# 11_DDR2.net
KiCad netlist of a schematic drawn in Altium Designer
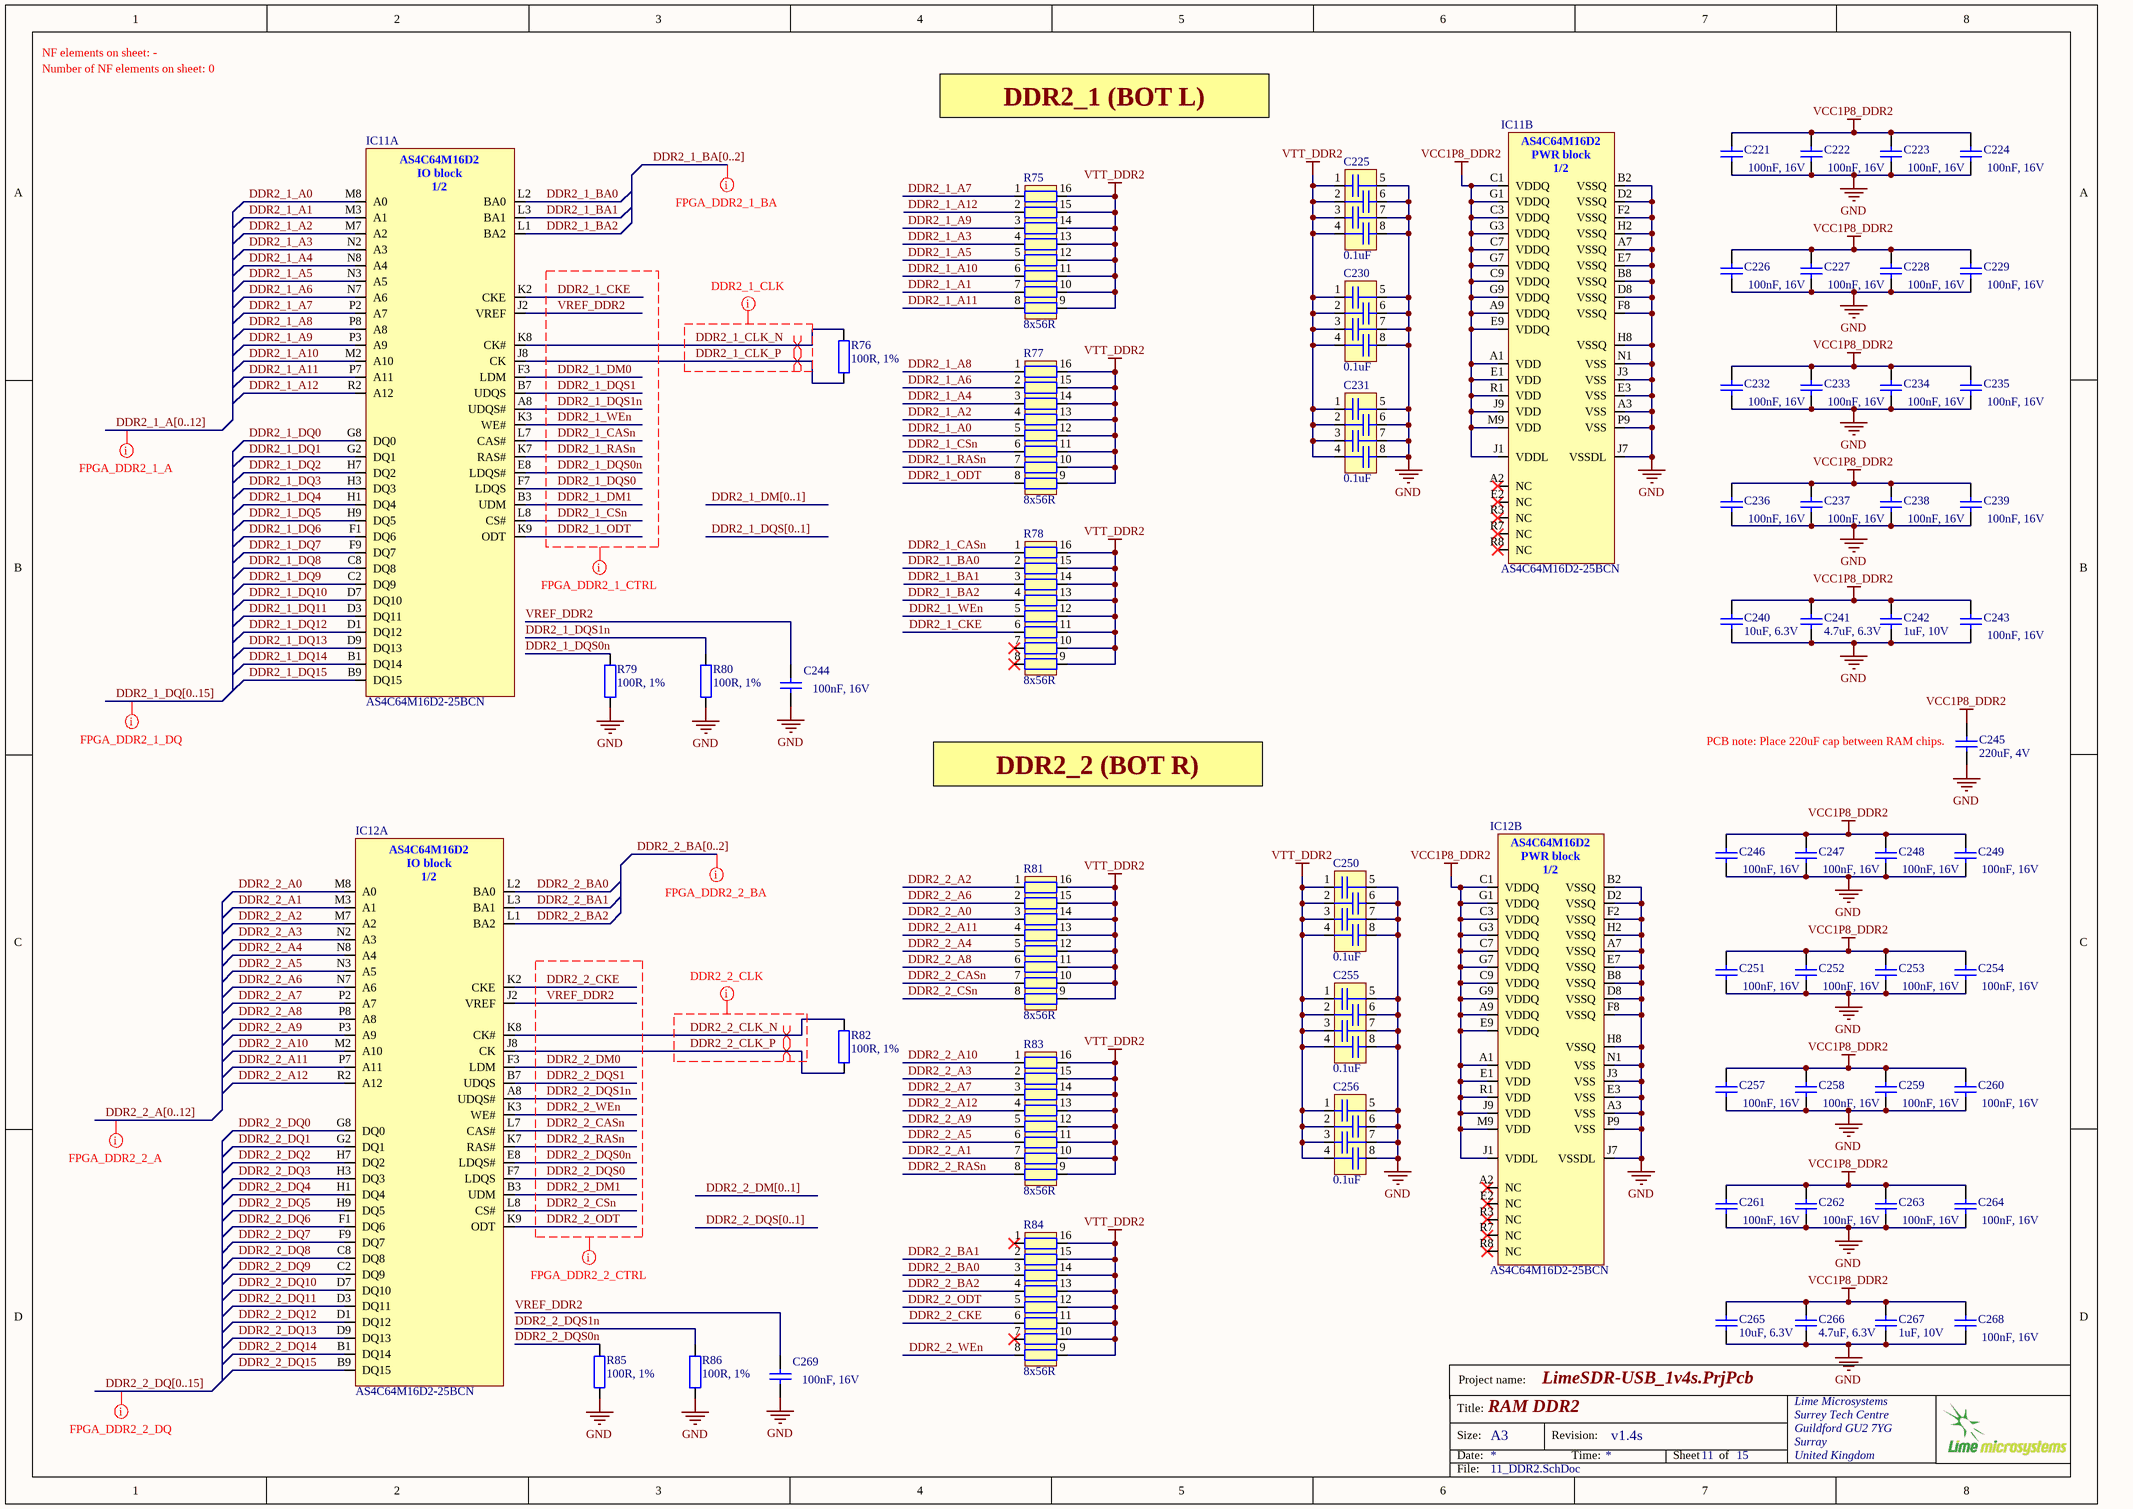
[diagram p0: 11_DDR2.SchDoc]

(export (version "E")
  (design (tool "Eeschema 10.0.6"))
  (components
    (comp (ref "C221")
      (value "100nF, 16V")
      (footprint "CAP0402")
      (fields
        (field (name "TOLERANCE") "10 %")
        (field (name "MANUFACTURER") "Murata Electronics")
        (field (name "MANUFACTURER PART NUMBER") "GRM155R71C104KA88D")
      )
      (libsource (lib "LimeFPGAboard_schLib") (part "Cap_0603"))
    )
    (comp (ref "C222")
      (value "100nF, 16V")
      (footprint "CAP0402")
      (fields
        (field (name "TOLERANCE") "10 %")
        (field (name "MANUFACTURER") "Murata Electronics")
        (field (name "MANUFACTURER PART NUMBER") "GRM155R71C104KA88D")
      )
      (libsource (lib "LimeFPGAboard_schLib") (part "Cap_0603"))
    )
    (comp (ref "C223")
      (value "100nF, 16V")
      (footprint "CAP0402")
      (fields
        (field (name "TOLERANCE") "10 %")
        (field (name "MANUFACTURER") "Murata Electronics")
        (field (name "MANUFACTURER PART NUMBER") "GRM155R71C104KA88D")
      )
      (libsource (lib "LimeFPGAboard_schLib") (part "Cap_0603"))
    )
    (comp (ref "C224")
      (value "100nF, 16V")
      (footprint "CAP0402")
      (fields
        (field (name "TOLERANCE") "10 %")
        (field (name "MANUFACTURER") "Murata Electronics")
        (field (name "MANUFACTURER PART NUMBER") "GRM155R71C104KA88D")
      )
      (libsource (lib "LimeFPGAboard_schLib") (part "Cap_0603"))
    )
    (comp (ref "C225")
      (value "0.1uF")
      (footprint "CKCA43X7R1C104M100AA")
      (fields (field (name "MANUFACTURER") "TDK") (field (name "TOLERANCE") "20 %"))
      (libsource (lib "LimeFPGAboard_schLib") (part "4X_cap_array_1206"))
    )
    (comp (ref "C226")
      (value "100nF, 16V")
      (footprint "CAP0402")
      (fields
        (field (name "TOLERANCE") "10 %")
        (field (name "MANUFACTURER") "Murata Electronics")
        (field (name "MANUFACTURER PART NUMBER") "GRM155R71C104KA88D")
      )
      (libsource (lib "LimeFPGAboard_schLib") (part "Cap_0603"))
    )
    (comp (ref "C227")
      (value "100nF, 16V")
      (footprint "CAP0402")
      (fields
        (field (name "TOLERANCE") "10 %")
        (field (name "MANUFACTURER") "Murata Electronics")
        (field (name "MANUFACTURER PART NUMBER") "GRM155R71C104KA88D")
      )
      (libsource (lib "LimeFPGAboard_schLib") (part "Cap_0603"))
    )
    (comp (ref "C228")
      (value "100nF, 16V")
      (footprint "CAP0402")
      (fields
        (field (name "TOLERANCE") "10 %")
        (field (name "MANUFACTURER") "Murata Electronics")
        (field (name "MANUFACTURER PART NUMBER") "GRM155R71C104KA88D")
      )
      (libsource (lib "LimeFPGAboard_schLib") (part "Cap_0603"))
    )
    (comp (ref "C229")
      (value "100nF, 16V")
      (footprint "CAP0402")
      (fields
        (field (name "TOLERANCE") "10 %")
        (field (name "MANUFACTURER") "Murata Electronics")
        (field (name "MANUFACTURER PART NUMBER") "GRM155R71C104KA88D")
      )
      (libsource (lib "LimeFPGAboard_schLib") (part "Cap_0603"))
    )
    (comp (ref "C230")
      (value "0.1uF")
      (footprint "CKCA43X7R1C104M100AA")
      (fields (field (name "MANUFACTURER") "TDK") (field (name "TOLERANCE") "20 %"))
      (libsource (lib "LimeFPGAboard_schLib") (part "4X_cap_array_1206"))
    )
    (comp (ref "C231")
      (value "0.1uF")
      (footprint "CKCA43X7R1C104M100AA")
      (fields (field (name "MANUFACTURER") "TDK") (field (name "TOLERANCE") "20 %"))
      (libsource (lib "LimeFPGAboard_schLib") (part "4X_cap_array_1206"))
    )
    (comp (ref "C232")
      (value "100nF, 16V")
      (footprint "CAP0402")
      (fields
        (field (name "TOLERANCE") "10 %")
        (field (name "MANUFACTURER") "Murata Electronics")
        (field (name "MANUFACTURER PART NUMBER") "GRM155R71C104KA88D")
      )
      (libsource (lib "LimeFPGAboard_schLib") (part "Cap_0603"))
    )
    (comp (ref "C233")
      (value "100nF, 16V")
      (footprint "CAP0402")
      (fields
        (field (name "TOLERANCE") "10 %")
        (field (name "MANUFACTURER") "Murata Electronics")
        (field (name "MANUFACTURER PART NUMBER") "GRM155R71C104KA88D")
      )
      (libsource (lib "LimeFPGAboard_schLib") (part "Cap_0603"))
    )
    (comp (ref "C234")
      (value "100nF, 16V")
      (footprint "CAP0402")
      (fields
        (field (name "TOLERANCE") "10 %")
        (field (name "MANUFACTURER") "Murata Electronics")
        (field (name "MANUFACTURER PART NUMBER") "GRM155R71C104KA88D")
      )
      (libsource (lib "LimeFPGAboard_schLib") (part "Cap_0603"))
    )
    (comp (ref "C235")
      (value "100nF, 16V")
      (footprint "CAP0402")
      (fields
        (field (name "TOLERANCE") "10 %")
        (field (name "MANUFACTURER") "Murata Electronics")
        (field (name "MANUFACTURER PART NUMBER") "GRM155R71C104KA88D")
      )
      (libsource (lib "LimeFPGAboard_schLib") (part "Cap_0603"))
    )
    (comp (ref "C236")
      (value "100nF, 16V")
      (footprint "CAP0402")
      (fields
        (field (name "TOLERANCE") "10 %")
        (field (name "MANUFACTURER") "Murata Electronics")
        (field (name "MANUFACTURER PART NUMBER") "GRM155R71C104KA88D")
      )
      (libsource (lib "LimeFPGAboard_schLib") (part "Cap_0603"))
    )
    (comp (ref "C237")
      (value "100nF, 16V")
      (footprint "CAP0402")
      (fields
        (field (name "TOLERANCE") "10 %")
        (field (name "MANUFACTURER") "Murata Electronics")
        (field (name "MANUFACTURER PART NUMBER") "GRM155R71C104KA88D")
      )
      (libsource (lib "LimeFPGAboard_schLib") (part "Cap_0603"))
    )
    (comp (ref "C238")
      (value "100nF, 16V")
      (footprint "CAP0402")
      (fields
        (field (name "TOLERANCE") "10 %")
        (field (name "MANUFACTURER") "Murata Electronics")
        (field (name "MANUFACTURER PART NUMBER") "GRM155R71C104KA88D")
      )
      (libsource (lib "LimeFPGAboard_schLib") (part "Cap_0603"))
    )
    (comp (ref "C239")
      (value "100nF, 16V")
      (footprint "CAP0402")
      (fields
        (field (name "TOLERANCE") "10 %")
        (field (name "MANUFACTURER") "Murata Electronics")
        (field (name "MANUFACTURER PART NUMBER") "GRM155R71C104KA88D")
      )
      (libsource (lib "LimeFPGAboard_schLib") (part "Cap_0603"))
    )
    (comp (ref "C240")
      (value "10uF, 6.3V")
      (footprint "CAP0603")
      (fields (field (name "TOLERANCE") "±20%") (field (name "MANUFACTURER") "Yageo"))
      (libsource (lib "LimeFPGAboard_schLib") (part "Cap_0603"))
    )
    (comp (ref "C241")
      (value "4.7uF, 6.3V")
      (footprint "CAP0402")
      (fields
        (field (name "MANUFACTURER") "Murata Electronics North America")
        (field (name "TOLERANCE") "±20%")
        (field (name "MANUFACTURER PART NUMBER") "GRM155R60J475ME87D")
      )
      (libsource (lib "LimeMicroAltiumLib_schLib") (part "Cap_0402"))
    )
    (comp (ref "C242")
      (value "1uF, 10V")
      (footprint "CAP0402")
      (fields (field (name "MANUFACTURER") "TDK"))
      (libsource (lib "LimeMicroAltiumLib_schLib") (part "Cap_0402"))
    )
    (comp (ref "C243")
      (value "100nF, 16V")
      (footprint "CAP0402")
      (fields
        (field (name "TOLERANCE") "10 %")
        (field (name "MANUFACTURER") "Murata Electronics")
        (field (name "MANUFACTURER PART NUMBER") "GRM155R71C104KA88D")
      )
      (libsource (lib "LimeFPGAboard_schLib") (part "Cap_0603"))
    )
    (comp (ref "C244")
      (value "100nF, 16V")
      (footprint "CAP0402")
      (fields
        (field (name "TOLERANCE") "10 %")
        (field (name "MANUFACTURER") "Murata Electronics")
        (field (name "MANUFACTURER PART NUMBER") "GRM155R71C104KA88D")
      )
      (libsource (lib "LimeFPGAboard_schLib") (part "Cap_0603"))
    )
    (comp (ref "C245")
      (value "220uF, 4V")
      (footprint "CAP1206")
      (fields
        (field (name "MANUFACTURER PART NUMBER") "GRM31CR60G227ME11L")
        (field (name "MANUFACTURER") "Murata Electronics North America")
        (field (name "TOLERANCE") "±20%")
      )
      (libsource (lib "LimeFPGAboard_schLib") (part "Cap_1206"))
    )
    (comp (ref "C246")
      (value "100nF, 16V")
      (footprint "CAP0402")
      (fields
        (field (name "TOLERANCE") "10 %")
        (field (name "MANUFACTURER") "Murata Electronics")
        (field (name "MANUFACTURER PART NUMBER") "GRM155R71C104KA88D")
      )
      (libsource (lib "LimeFPGAboard_schLib") (part "Cap_0603"))
    )
    (comp (ref "C247")
      (value "100nF, 16V")
      (footprint "CAP0402")
      (fields
        (field (name "TOLERANCE") "10 %")
        (field (name "MANUFACTURER") "Murata Electronics")
        (field (name "MANUFACTURER PART NUMBER") "GRM155R71C104KA88D")
      )
      (libsource (lib "LimeFPGAboard_schLib") (part "Cap_0603"))
    )
    (comp (ref "C248")
      (value "100nF, 16V")
      (footprint "CAP0402")
      (fields
        (field (name "TOLERANCE") "10 %")
        (field (name "MANUFACTURER") "Murata Electronics")
        (field (name "MANUFACTURER PART NUMBER") "GRM155R71C104KA88D")
      )
      (libsource (lib "LimeFPGAboard_schLib") (part "Cap_0603"))
    )
    (comp (ref "C249")
      (value "100nF, 16V")
      (footprint "CAP0402")
      (fields
        (field (name "TOLERANCE") "10 %")
        (field (name "MANUFACTURER") "Murata Electronics")
        (field (name "MANUFACTURER PART NUMBER") "GRM155R71C104KA88D")
      )
      (libsource (lib "LimeFPGAboard_schLib") (part "Cap_0603"))
    )
    (comp (ref "C250")
      (value "0.1uF")
      (footprint "CKCA43X7R1C104M100AA")
      (fields (field (name "MANUFACTURER") "TDK") (field (name "TOLERANCE") "20 %"))
      (libsource (lib "LimeFPGAboard_schLib") (part "4X_cap_array_1206"))
    )
    (comp (ref "C251")
      (value "100nF, 16V")
      (footprint "CAP0402")
      (fields
        (field (name "TOLERANCE") "10 %")
        (field (name "MANUFACTURER") "Murata Electronics")
        (field (name "MANUFACTURER PART NUMBER") "GRM155R71C104KA88D")
      )
      (libsource (lib "LimeFPGAboard_schLib") (part "Cap_0603"))
    )
    (comp (ref "C252")
      (value "100nF, 16V")
      (footprint "CAP0402")
      (fields
        (field (name "TOLERANCE") "10 %")
        (field (name "MANUFACTURER") "Murata Electronics")
        (field (name "MANUFACTURER PART NUMBER") "GRM155R71C104KA88D")
      )
      (libsource (lib "LimeFPGAboard_schLib") (part "Cap_0603"))
    )
    (comp (ref "C253")
      (value "100nF, 16V")
      (footprint "CAP0402")
      (fields
        (field (name "TOLERANCE") "10 %")
        (field (name "MANUFACTURER") "Murata Electronics")
        (field (name "MANUFACTURER PART NUMBER") "GRM155R71C104KA88D")
      )
      (libsource (lib "LimeFPGAboard_schLib") (part "Cap_0603"))
    )
    (comp (ref "C254")
      (value "100nF, 16V")
      (footprint "CAP0402")
      (fields
        (field (name "TOLERANCE") "10 %")
        (field (name "MANUFACTURER") "Murata Electronics")
        (field (name "MANUFACTURER PART NUMBER") "GRM155R71C104KA88D")
      )
      (libsource (lib "LimeFPGAboard_schLib") (part "Cap_0603"))
    )
    (comp (ref "C255")
      (value "0.1uF")
      (footprint "CKCA43X7R1C104M100AA")
      (fields (field (name "MANUFACTURER") "TDK") (field (name "TOLERANCE") "20 %"))
      (libsource (lib "LimeFPGAboard_schLib") (part "4X_cap_array_1206"))
    )
    (comp (ref "C256")
      (value "0.1uF")
      (footprint "CKCA43X7R1C104M100AA")
      (fields (field (name "MANUFACTURER") "TDK") (field (name "TOLERANCE") "20 %"))
      (libsource (lib "LimeFPGAboard_schLib") (part "4X_cap_array_1206"))
    )
    (comp (ref "C257")
      (value "100nF, 16V")
      (footprint "CAP0402")
      (fields
        (field (name "TOLERANCE") "10 %")
        (field (name "MANUFACTURER") "Murata Electronics")
        (field (name "MANUFACTURER PART NUMBER") "GRM155R71C104KA88D")
      )
      (libsource (lib "LimeFPGAboard_schLib") (part "Cap_0603"))
    )
    (comp (ref "C258")
      (value "100nF, 16V")
      (footprint "CAP0402")
      (fields
        (field (name "TOLERANCE") "10 %")
        (field (name "MANUFACTURER") "Murata Electronics")
        (field (name "MANUFACTURER PART NUMBER") "GRM155R71C104KA88D")
      )
      (libsource (lib "LimeFPGAboard_schLib") (part "Cap_0603"))
    )
    (comp (ref "C259")
      (value "100nF, 16V")
      (footprint "CAP0402")
      (fields
        (field (name "TOLERANCE") "10 %")
        (field (name "MANUFACTURER") "Murata Electronics")
        (field (name "MANUFACTURER PART NUMBER") "GRM155R71C104KA88D")
      )
      (libsource (lib "LimeFPGAboard_schLib") (part "Cap_0603"))
    )
    (comp (ref "C260")
      (value "100nF, 16V")
      (footprint "CAP0402")
      (fields
        (field (name "TOLERANCE") "10 %")
        (field (name "MANUFACTURER") "Murata Electronics")
        (field (name "MANUFACTURER PART NUMBER") "GRM155R71C104KA88D")
      )
      (libsource (lib "LimeFPGAboard_schLib") (part "Cap_0603"))
    )
    (comp (ref "C261")
      (value "100nF, 16V")
      (footprint "CAP0402")
      (fields
        (field (name "TOLERANCE") "10 %")
        (field (name "MANUFACTURER") "Murata Electronics")
        (field (name "MANUFACTURER PART NUMBER") "GRM155R71C104KA88D")
      )
      (libsource (lib "LimeFPGAboard_schLib") (part "Cap_0603"))
    )
    (comp (ref "C262")
      (value "100nF, 16V")
      (footprint "CAP0402")
      (fields
        (field (name "TOLERANCE") "10 %")
        (field (name "MANUFACTURER") "Murata Electronics")
        (field (name "MANUFACTURER PART NUMBER") "GRM155R71C104KA88D")
      )
      (libsource (lib "LimeFPGAboard_schLib") (part "Cap_0603"))
    )
    (comp (ref "C263")
      (value "100nF, 16V")
      (footprint "CAP0402")
      (fields
        (field (name "TOLERANCE") "10 %")
        (field (name "MANUFACTURER") "Murata Electronics")
        (field (name "MANUFACTURER PART NUMBER") "GRM155R71C104KA88D")
      )
      (libsource (lib "LimeFPGAboard_schLib") (part "Cap_0603"))
    )
    (comp (ref "C264")
      (value "100nF, 16V")
      (footprint "CAP0402")
      (fields
        (field (name "TOLERANCE") "10 %")
        (field (name "MANUFACTURER") "Murata Electronics")
        (field (name "MANUFACTURER PART NUMBER") "GRM155R71C104KA88D")
      )
      (libsource (lib "LimeFPGAboard_schLib") (part "Cap_0603"))
    )
    (comp (ref "C265")
      (value "10uF, 6.3V")
      (footprint "CAP0603")
      (fields (field (name "TOLERANCE") "±20%") (field (name "MANUFACTURER") "Yageo"))
      (libsource (lib "LimeFPGAboard_schLib") (part "Cap_0603"))
    )
    (comp (ref "C266")
      (value "4.7uF, 6.3V")
      (footprint "CAP0402")
      (fields
        (field (name "MANUFACTURER") "Murata Electronics North America")
        (field (name "TOLERANCE") "±20%")
        (field (name "MANUFACTURER PART NUMBER") "GRM155R60J475ME87D")
      )
      (libsource (lib "LimeMicroAltiumLib_schLib") (part "Cap_0402"))
    )
    (comp (ref "C267")
      (value "1uF, 10V")
      (footprint "CAP0402")
      (fields (field (name "MANUFACTURER") "TDK"))
      (libsource (lib "LimeMicroAltiumLib_schLib") (part "Cap_0402"))
    )
    (comp (ref "C268")
      (value "100nF, 16V")
      (footprint "CAP0402")
      (fields
        (field (name "TOLERANCE") "10 %")
        (field (name "MANUFACTURER") "Murata Electronics")
        (field (name "MANUFACTURER PART NUMBER") "GRM155R71C104KA88D")
      )
      (libsource (lib "LimeFPGAboard_schLib") (part "Cap_0603"))
    )
    (comp (ref "C269")
      (value "100nF, 16V")
      (footprint "CAP0402")
      (fields
        (field (name "TOLERANCE") "10 %")
        (field (name "MANUFACTURER") "Murata Electronics")
        (field (name "MANUFACTURER PART NUMBER") "GRM155R71C104KA88D")
      )
      (libsource (lib "LimeFPGAboard_schLib") (part "Cap_0603"))
    )
    (comp (ref "IC11")
      (value "AS4C64M16D2-25BCN")
      (footprint "AS4C64M16D2")
      (fields (field (name "MANUFACTURER") "Alliance Memory, Inc."))
      (libsource (lib "LimeMicroAltiumLib_schLib") (part "AS4C64M16D2-25BCN"))
    )
    (comp (ref "IC12")
      (value "AS4C64M16D2-25BCN")
      (footprint "AS4C64M16D2")
      (fields (field (name "MANUFACTURER") "Alliance Memory, Inc."))
      (libsource (lib "LimeMicroAltiumLib_schLib") (part "AS4C64M16D2-25BCN"))
    )
    (comp (ref "R75")
      (value "8x56R")
      (footprint "EXB2HV")
      (fields (field (name "MANUFACTURER") "PANASONIC ELECTRONIC COMPONENTS"))
      (libsource (lib "LimeFPGAboard_schLib") (part "8X_resistor_array_0402"))
    )
    (comp (ref "R76")
      (value "100R, 1%")
      (footprint "RES0402")
      (fields (field (name "TOLERANCE") "±1%") (field (name "MANUFACTURER") "Stackpole Electronics Inc."))
      (libsource (lib "LimeFPGAboard_schLib") (part "Res_0402"))
    )
    (comp (ref "R77")
      (value "8x56R")
      (footprint "EXB2HV")
      (fields (field (name "MANUFACTURER") "PANASONIC ELECTRONIC COMPONENTS"))
      (libsource (lib "LimeFPGAboard_schLib") (part "8X_resistor_array_0402"))
    )
    (comp (ref "R78")
      (value "8x56R")
      (footprint "EXB2HV")
      (fields (field (name "MANUFACTURER") "PANASONIC ELECTRONIC COMPONENTS"))
      (libsource (lib "LimeFPGAboard_schLib") (part "8X_resistor_array_0402"))
    )
    (comp (ref "R79")
      (value "100R, 1%")
      (footprint "RES0402")
      (fields (field (name "TOLERANCE") "±1%") (field (name "MANUFACTURER") "Stackpole Electronics Inc."))
      (libsource (lib "LimeFPGAboard_schLib") (part "Res_0402"))
    )
    (comp (ref "R80")
      (value "100R, 1%")
      (footprint "RES0402")
      (fields (field (name "TOLERANCE") "±1%") (field (name "MANUFACTURER") "Stackpole Electronics Inc."))
      (libsource (lib "LimeFPGAboard_schLib") (part "Res_0402"))
    )
    (comp (ref "R81")
      (value "8x56R")
      (footprint "EXB2HV")
      (fields (field (name "MANUFACTURER") "PANASONIC ELECTRONIC COMPONENTS"))
      (libsource (lib "LimeFPGAboard_schLib") (part "8X_resistor_array_0402"))
    )
    (comp (ref "R82")
      (value "100R, 1%")
      (footprint "RES0402")
      (fields (field (name "TOLERANCE") "±1%") (field (name "MANUFACTURER") "Stackpole Electronics Inc."))
      (libsource (lib "LimeFPGAboard_schLib") (part "Res_0402"))
    )
    (comp (ref "R83")
      (value "8x56R")
      (footprint "EXB2HV")
      (fields (field (name "MANUFACTURER") "PANASONIC ELECTRONIC COMPONENTS"))
      (libsource (lib "LimeFPGAboard_schLib") (part "8X_resistor_array_0402"))
    )
    (comp (ref "R84")
      (value "8x56R")
      (footprint "EXB2HV")
      (fields (field (name "MANUFACTURER") "PANASONIC ELECTRONIC COMPONENTS"))
      (libsource (lib "LimeFPGAboard_schLib") (part "8X_resistor_array_0402"))
    )
    (comp (ref "R85")
      (value "100R, 1%")
      (footprint "RES0402")
      (fields (field (name "TOLERANCE") "±1%") (field (name "MANUFACTURER") "Stackpole Electronics Inc."))
      (libsource (lib "LimeFPGAboard_schLib") (part "Res_0402"))
    )
    (comp (ref "R86")
      (value "100R, 1%")
      (footprint "RES0402")
      (fields (field (name "TOLERANCE") "±1%") (field (name "MANUFACTURER") "Stackpole Electronics Inc."))
      (libsource (lib "LimeFPGAboard_schLib") (part "Res_0402"))
    )
  )
  (nets
    (net (code "1") (name "/DDR2_1_A0") (class "Default")
      (node (ref "IC11") (pin "M8") (pinfunction "A0_M8") (pintype "passive"))
      (node (ref "R77") (pin "5") (pinfunction "5_5") (pintype "passive"))
    )
    (net (code "2") (name "/DDR2_1_A1") (class "Default")
      (node (ref "IC11") (pin "M3") (pinfunction "A1_M3") (pintype "passive"))
      (node (ref "R75") (pin "7") (pinfunction "7_7") (pintype "passive"))
    )
    (net (code "3") (name "/DDR2_1_A2") (class "Default")
      (node (ref "IC11") (pin "M7") (pinfunction "A2_M7") (pintype "passive"))
      (node (ref "R77") (pin "4") (pinfunction "4_4") (pintype "passive"))
    )
    (net (code "4") (name "/DDR2_1_A3") (class "Default")
      (node (ref "IC11") (pin "N2") (pinfunction "A3_N2") (pintype "passive"))
      (node (ref "R75") (pin "4") (pinfunction "4_4") (pintype "passive"))
    )
    (net (code "5") (name "/DDR2_1_A4") (class "Default")
      (node (ref "IC11") (pin "N8") (pinfunction "A4_N8") (pintype "passive"))
      (node (ref "R77") (pin "3") (pinfunction "3_3") (pintype "passive"))
    )
    (net (code "6") (name "/DDR2_1_A5") (class "Default")
      (node (ref "IC11") (pin "N3") (pinfunction "A5_N3") (pintype "passive"))
      (node (ref "R75") (pin "5") (pinfunction "5_5") (pintype "passive"))
    )
    (net (code "7") (name "/DDR2_1_A6") (class "Default")
      (node (ref "IC11") (pin "N7") (pinfunction "A6_N7") (pintype "passive"))
      (node (ref "R77") (pin "2") (pinfunction "2_2") (pintype "passive"))
    )
    (net (code "8") (name "/DDR2_1_A7") (class "Default")
      (node (ref "IC11") (pin "P2") (pinfunction "A7_P2") (pintype "passive"))
      (node (ref "R75") (pin "1") (pinfunction "1_1") (pintype "passive"))
    )
    (net (code "9") (name "/DDR2_1_A8") (class "Default")
      (node (ref "IC11") (pin "P8") (pinfunction "A8_P8") (pintype "passive"))
      (node (ref "R77") (pin "1") (pinfunction "1_1") (pintype "passive"))
    )
    (net (code "10") (name "/DDR2_1_A9") (class "Default")
      (node (ref "IC11") (pin "P3") (pinfunction "A9_P3") (pintype "passive"))
      (node (ref "R75") (pin "3") (pinfunction "3_3") (pintype "passive"))
    )
    (net (code "11") (name "/DDR2_1_A10") (class "Default")
      (node (ref "IC11") (pin "M2") (pinfunction "A10_M2") (pintype "passive"))
      (node (ref "R75") (pin "6") (pinfunction "6_6") (pintype "passive"))
    )
    (net (code "12") (name "/DDR2_1_A11") (class "Default")
      (node (ref "IC11") (pin "P7") (pinfunction "A11_P7") (pintype "passive"))
      (node (ref "R75") (pin "8") (pinfunction "8_8") (pintype "passive"))
    )
    (net (code "13") (name "/DDR2_1_A12") (class "Default")
      (node (ref "IC11") (pin "R2") (pinfunction "A12_R2") (pintype "passive"))
      (node (ref "R75") (pin "2") (pinfunction "2_2") (pintype "passive"))
    )
    (net (code "15") (name "/DDR2_1_BA0") (class "Default")
      (node (ref "IC11") (pin "L2") (pinfunction "BA0_L2") (pintype "passive"))
      (node (ref "R78") (pin "2") (pinfunction "2_2") (pintype "passive"))
    )
    (net (code "16") (name "/DDR2_1_BA1") (class "Default")
      (node (ref "IC11") (pin "L3") (pinfunction "BA1_L3") (pintype "passive"))
      (node (ref "R78") (pin "3") (pinfunction "3_3") (pintype "passive"))
    )
    (net (code "17") (name "/DDR2_1_BA2") (class "Default")
      (node (ref "IC11") (pin "L1") (pinfunction "BA2_L1") (pintype "passive"))
      (node (ref "R78") (pin "4") (pinfunction "4_4") (pintype "passive"))
    )
    (net (code "19") (name "/DDR2_1_CASn") (class "Default")
      (node (ref "IC11") (pin "L7") (pinfunction "CAS#_L7") (pintype "passive"))
      (node (ref "R78") (pin "1") (pinfunction "1_1") (pintype "passive"))
    )
    (net (code "20") (name "/DDR2_1_CKE") (class "Default")
      (node (ref "IC11") (pin "K2") (pinfunction "CKE_K2") (pintype "passive"))
      (node (ref "R78") (pin "6") (pinfunction "6_6") (pintype "passive"))
    )
    (net (code "21") (name "/DDR2_1_CLK_N") (class "Default")
      (node (ref "IC11") (pin "K8") (pinfunction "CK#_K8") (pintype "passive"))
      (node (ref "R76") (pin "2") (pinfunction "2_2") (pintype "passive"))
    )
    (net (code "22") (name "/DDR2_1_CLK_P") (class "Default")
      (node (ref "IC11") (pin "J8") (pinfunction "CK_J8") (pintype "passive"))
      (node (ref "R76") (pin "1") (pinfunction "1_1") (pintype "passive"))
    )
    (net (code "23") (name "/DDR2_1_CSn") (class "Default")
      (node (ref "IC11") (pin "L8") (pinfunction "CS#_L8") (pintype "passive"))
      (node (ref "R77") (pin "6") (pinfunction "6_6") (pintype "passive"))
    )
    (net (code "24") (name "/DDR2_1_DM0") (class "Default")
      (node (ref "IC11") (pin "F3") (pinfunction "LDM_F3") (pintype "passive"))
    )
    (net (code "25") (name "/DDR2_1_DM1") (class "Default")
      (node (ref "IC11") (pin "B3") (pinfunction "UDM_B3") (pintype "passive"))
    )
    (net (code "27") (name "/DDR2_1_DQ0") (class "Default")
      (node (ref "IC11") (pin "G8") (pinfunction "DQ0_G8") (pintype "passive"))
    )
    (net (code "28") (name "/DDR2_1_DQ1") (class "Default")
      (node (ref "IC11") (pin "G2") (pinfunction "DQ1_G2") (pintype "passive"))
    )
    (net (code "29") (name "/DDR2_1_DQ2") (class "Default")
      (node (ref "IC11") (pin "H7") (pinfunction "DQ2_H7") (pintype "passive"))
    )
    (net (code "30") (name "/DDR2_1_DQ3") (class "Default")
      (node (ref "IC11") (pin "H3") (pinfunction "DQ3_H3") (pintype "passive"))
    )
    (net (code "31") (name "/DDR2_1_DQ4") (class "Default")
      (node (ref "IC11") (pin "H1") (pinfunction "DQ4_H1") (pintype "passive"))
    )
    (net (code "32") (name "/DDR2_1_DQ5") (class "Default")
      (node (ref "IC11") (pin "H9") (pinfunction "DQ5_H9") (pintype "passive"))
    )
    (net (code "33") (name "/DDR2_1_DQ6") (class "Default")
      (node (ref "IC11") (pin "F1") (pinfunction "DQ6_F1") (pintype "passive"))
    )
    (net (code "34") (name "/DDR2_1_DQ7") (class "Default")
      (node (ref "IC11") (pin "F9") (pinfunction "DQ7_F9") (pintype "passive"))
    )
    (net (code "35") (name "/DDR2_1_DQ8") (class "Default")
      (node (ref "IC11") (pin "C8") (pinfunction "DQ8_C8") (pintype "passive"))
    )
    (net (code "36") (name "/DDR2_1_DQ9") (class "Default")
      (node (ref "IC11") (pin "C2") (pinfunction "DQ9_C2") (pintype "passive"))
    )
    (net (code "37") (name "/DDR2_1_DQ10") (class "Default")
      (node (ref "IC11") (pin "D7") (pinfunction "DQ10_D7") (pintype "passive"))
    )
    (net (code "38") (name "/DDR2_1_DQ11") (class "Default")
      (node (ref "IC11") (pin "D3") (pinfunction "DQ11_D3") (pintype "passive"))
    )
    (net (code "39") (name "/DDR2_1_DQ12") (class "Default")
      (node (ref "IC11") (pin "D1") (pinfunction "DQ12_D1") (pintype "passive"))
    )
    (net (code "40") (name "/DDR2_1_DQ13") (class "Default")
      (node (ref "IC11") (pin "D9") (pinfunction "DQ13_D9") (pintype "passive"))
    )
    (net (code "41") (name "/DDR2_1_DQ14") (class "Default")
      (node (ref "IC11") (pin "B1") (pinfunction "DQ14_B1") (pintype "passive"))
    )
    (net (code "42") (name "/DDR2_1_DQ15") (class "Default")
      (node (ref "IC11") (pin "B9") (pinfunction "DQ15_B9") (pintype "passive"))
    )
    (net (code "43") (name "/DDR2_1_DQS0") (class "Default")
      (node (ref "IC11") (pin "F7") (pinfunction "LDQS_F7") (pintype "passive"))
    )
    (net (code "44") (name "/DDR2_1_DQS0n") (class "Default")
      (node (ref "IC11") (pin "E8") (pinfunction "LDQS#_E8") (pintype "passive"))
      (node (ref "R79") (pin "2") (pinfunction "2_2") (pintype "passive"))
    )
    (net (code "45") (name "/DDR2_1_DQS1") (class "Default")
      (node (ref "IC11") (pin "B7") (pinfunction "UDQS_B7") (pintype "passive"))
    )
    (net (code "46") (name "/DDR2_1_DQS1n") (class "Default")
      (node (ref "IC11") (pin "A8") (pinfunction "UDQS#_A8") (pintype "passive"))
      (node (ref "R80") (pin "2") (pinfunction "2_2") (pintype "passive"))
    )
    (net (code "49") (name "/DDR2_1_ODT") (class "Default")
      (node (ref "IC11") (pin "K9") (pinfunction "ODT_K9") (pintype "passive"))
      (node (ref "R77") (pin "8") (pinfunction "8_8") (pintype "passive"))
    )
    (net (code "50") (name "/DDR2_1_RASn") (class "Default")
      (node (ref "IC11") (pin "K7") (pinfunction "RAS#_K7") (pintype "passive"))
      (node (ref "R77") (pin "7") (pinfunction "7_7") (pintype "passive"))
    )
    (net (code "51") (name "/DDR2_1_WEn") (class "Default")
      (node (ref "IC11") (pin "K3") (pinfunction "WE#_K3") (pintype "passive"))
      (node (ref "R78") (pin "5") (pinfunction "5_5") (pintype "passive"))
    )
    (net (code "52") (name "/DDR2_2_A0") (class "Default")
      (node (ref "IC12") (pin "M8") (pinfunction "A0_M8") (pintype "passive"))
      (node (ref "R81") (pin "3") (pinfunction "3_3") (pintype "passive"))
    )
    (net (code "53") (name "/DDR2_2_A1") (class "Default")
      (node (ref "IC12") (pin "M3") (pinfunction "A1_M3") (pintype "passive"))
      (node (ref "R83") (pin "7") (pinfunction "7_7") (pintype "passive"))
    )
    (net (code "54") (name "/DDR2_2_A2") (class "Default")
      (node (ref "IC12") (pin "M7") (pinfunction "A2_M7") (pintype "passive"))
      (node (ref "R81") (pin "1") (pinfunction "1_1") (pintype "passive"))
    )
    (net (code "55") (name "/DDR2_2_A3") (class "Default")
      (node (ref "IC12") (pin "N2") (pinfunction "A3_N2") (pintype "passive"))
      (node (ref "R83") (pin "2") (pinfunction "2_2") (pintype "passive"))
    )
    (net (code "56") (name "/DDR2_2_A4") (class "Default")
      (node (ref "IC12") (pin "N8") (pinfunction "A4_N8") (pintype "passive"))
      (node (ref "R81") (pin "5") (pinfunction "5_5") (pintype "passive"))
    )
    (net (code "57") (name "/DDR2_2_A5") (class "Default")
      (node (ref "IC12") (pin "N3") (pinfunction "A5_N3") (pintype "passive"))
      (node (ref "R83") (pin "6") (pinfunction "6_6") (pintype "passive"))
    )
    (net (code "58") (name "/DDR2_2_A6") (class "Default")
      (node (ref "IC12") (pin "N7") (pinfunction "A6_N7") (pintype "passive"))
      (node (ref "R81") (pin "2") (pinfunction "2_2") (pintype "passive"))
    )
    (net (code "59") (name "/DDR2_2_A7") (class "Default")
      (node (ref "IC12") (pin "P2") (pinfunction "A7_P2") (pintype "passive"))
      (node (ref "R83") (pin "3") (pinfunction "3_3") (pintype "passive"))
    )
    (net (code "60") (name "/DDR2_2_A8") (class "Default")
      (node (ref "IC12") (pin "P8") (pinfunction "A8_P8") (pintype "passive"))
      (node (ref "R81") (pin "6") (pinfunction "6_6") (pintype "passive"))
    )
    (net (code "61") (name "/DDR2_2_A9") (class "Default")
      (node (ref "IC12") (pin "P3") (pinfunction "A9_P3") (pintype "passive"))
      (node (ref "R83") (pin "5") (pinfunction "5_5") (pintype "passive"))
    )
    (net (code "62") (name "/DDR2_2_A10") (class "Default")
      (node (ref "IC12") (pin "M2") (pinfunction "A10_M2") (pintype "passive"))
      (node (ref "R83") (pin "1") (pinfunction "1_1") (pintype "passive"))
    )
    (net (code "63") (name "/DDR2_2_A11") (class "Default")
      (node (ref "IC12") (pin "P7") (pinfunction "A11_P7") (pintype "passive"))
      (node (ref "R81") (pin "4") (pinfunction "4_4") (pintype "passive"))
    )
    (net (code "64") (name "/DDR2_2_A12") (class "Default")
      (node (ref "IC12") (pin "R2") (pinfunction "A12_R2") (pintype "passive"))
      (node (ref "R83") (pin "4") (pinfunction "4_4") (pintype "passive"))
    )
    (net (code "66") (name "/DDR2_2_BA0") (class "Default")
      (node (ref "IC12") (pin "L2") (pinfunction "BA0_L2") (pintype "passive"))
      (node (ref "R84") (pin "3") (pinfunction "3_3") (pintype "passive"))
    )
    (net (code "67") (name "/DDR2_2_BA1") (class "Default")
      (node (ref "IC12") (pin "L3") (pinfunction "BA1_L3") (pintype "passive"))
      (node (ref "R84") (pin "2") (pinfunction "2_2") (pintype "passive"))
    )
    (net (code "68") (name "/DDR2_2_BA2") (class "Default")
      (node (ref "IC12") (pin "L1") (pinfunction "BA2_L1") (pintype "passive"))
      (node (ref "R84") (pin "4") (pinfunction "4_4") (pintype "passive"))
    )
    (net (code "70") (name "/DDR2_2_CASn") (class "Default")
      (node (ref "IC12") (pin "L7") (pinfunction "CAS#_L7") (pintype "passive"))
      (node (ref "R81") (pin "7") (pinfunction "7_7") (pintype "passive"))
    )
    (net (code "71") (name "/DDR2_2_CKE") (class "Default")
      (node (ref "IC12") (pin "K2") (pinfunction "CKE_K2") (pintype "passive"))
      (node (ref "R84") (pin "6") (pinfunction "6_6") (pintype "passive"))
    )
    (net (code "72") (name "/DDR2_2_CLK_N") (class "Default")
      (node (ref "IC12") (pin "K8") (pinfunction "CK#_K8") (pintype "passive"))
      (node (ref "R82") (pin "2") (pinfunction "2_2") (pintype "passive"))
    )
    (net (code "73") (name "/DDR2_2_CLK_P") (class "Default")
      (node (ref "IC12") (pin "J8") (pinfunction "CK_J8") (pintype "passive"))
      (node (ref "R82") (pin "1") (pinfunction "1_1") (pintype "passive"))
    )
    (net (code "74") (name "/DDR2_2_CSn") (class "Default")
      (node (ref "IC12") (pin "L8") (pinfunction "CS#_L8") (pintype "passive"))
      (node (ref "R81") (pin "8") (pinfunction "8_8") (pintype "passive"))
    )
    (net (code "75") (name "/DDR2_2_DM0") (class "Default")
      (node (ref "IC12") (pin "F3") (pinfunction "LDM_F3") (pintype "passive"))
    )
    (net (code "76") (name "/DDR2_2_DM1") (class "Default")
      (node (ref "IC12") (pin "B3") (pinfunction "UDM_B3") (pintype "passive"))
    )
    (net (code "78") (name "/DDR2_2_DQ0") (class "Default")
      (node (ref "IC12") (pin "G8") (pinfunction "DQ0_G8") (pintype "passive"))
    )
    (net (code "79") (name "/DDR2_2_DQ1") (class "Default")
      (node (ref "IC12") (pin "G2") (pinfunction "DQ1_G2") (pintype "passive"))
    )
    (net (code "80") (name "/DDR2_2_DQ2") (class "Default")
      (node (ref "IC12") (pin "H7") (pinfunction "DQ2_H7") (pintype "passive"))
    )
    (net (code "81") (name "/DDR2_2_DQ3") (class "Default")
      (node (ref "IC12") (pin "H3") (pinfunction "DQ3_H3") (pintype "passive"))
    )
    (net (code "82") (name "/DDR2_2_DQ4") (class "Default")
      (node (ref "IC12") (pin "H1") (pinfunction "DQ4_H1") (pintype "passive"))
    )
    (net (code "83") (name "/DDR2_2_DQ5") (class "Default")
      (node (ref "IC12") (pin "H9") (pinfunction "DQ5_H9") (pintype "passive"))
    )
    (net (code "84") (name "/DDR2_2_DQ6") (class "Default")
      (node (ref "IC12") (pin "F1") (pinfunction "DQ6_F1") (pintype "passive"))
    )
    (net (code "85") (name "/DDR2_2_DQ7") (class "Default")
      (node (ref "IC12") (pin "F9") (pinfunction "DQ7_F9") (pintype "passive"))
    )
    (net (code "86") (name "/DDR2_2_DQ8") (class "Default")
      (node (ref "IC12") (pin "C8") (pinfunction "DQ8_C8") (pintype "passive"))
    )
    (net (code "87") (name "/DDR2_2_DQ9") (class "Default")
      (node (ref "IC12") (pin "C2") (pinfunction "DQ9_C2") (pintype "passive"))
    )
    (net (code "88") (name "/DDR2_2_DQ10") (class "Default")
      (node (ref "IC12") (pin "D7") (pinfunction "DQ10_D7") (pintype "passive"))
    )
    (net (code "89") (name "/DDR2_2_DQ11") (class "Default")
      (node (ref "IC12") (pin "D3") (pinfunction "DQ11_D3") (pintype "passive"))
    )
    (net (code "90") (name "/DDR2_2_DQ12") (class "Default")
      (node (ref "IC12") (pin "D1") (pinfunction "DQ12_D1") (pintype "passive"))
    )
    (net (code "91") (name "/DDR2_2_DQ13") (class "Default")
      (node (ref "IC12") (pin "D9") (pinfunction "DQ13_D9") (pintype "passive"))
    )
    (net (code "92") (name "/DDR2_2_DQ14") (class "Default")
      (node (ref "IC12") (pin "B1") (pinfunction "DQ14_B1") (pintype "passive"))
    )
    (net (code "93") (name "/DDR2_2_DQ15") (class "Default")
      (node (ref "IC12") (pin "B9") (pinfunction "DQ15_B9") (pintype "passive"))
    )
    (net (code "94") (name "/DDR2_2_DQS0") (class "Default")
      (node (ref "IC12") (pin "F7") (pinfunction "LDQS_F7") (pintype "passive"))
    )
    (net (code "95") (name "/DDR2_2_DQS0n") (class "Default")
      (node (ref "IC12") (pin "E8") (pinfunction "LDQS#_E8") (pintype "passive"))
      (node (ref "R85") (pin "2") (pinfunction "2_2") (pintype "passive"))
    )
    (net (code "96") (name "/DDR2_2_DQS1") (class "Default")
      (node (ref "IC12") (pin "B7") (pinfunction "UDQS_B7") (pintype "passive"))
    )
    (net (code "97") (name "/DDR2_2_DQS1n") (class "Default")
      (node (ref "IC12") (pin "A8") (pinfunction "UDQS#_A8") (pintype "passive"))
      (node (ref "R86") (pin "2") (pinfunction "2_2") (pintype "passive"))
    )
    (net (code "100") (name "/DDR2_2_ODT") (class "Default")
      (node (ref "IC12") (pin "K9") (pinfunction "ODT_K9") (pintype "passive"))
      (node (ref "R84") (pin "5") (pinfunction "5_5") (pintype "passive"))
    )
    (net (code "101") (name "/DDR2_2_RASn") (class "Default")
      (node (ref "IC12") (pin "K7") (pinfunction "RAS#_K7") (pintype "passive"))
      (node (ref "R83") (pin "8") (pinfunction "8_8") (pintype "passive"))
    )
    (net (code "102") (name "/DDR2_2_WEn") (class "Default")
      (node (ref "IC12") (pin "K3") (pinfunction "WE#_K3") (pintype "passive"))
      (node (ref "R84") (pin "8") (pinfunction "8_8") (pintype "passive"))
    )
    (net (code "103") (name "/VREF_DDR2") (class "Default")
      (node (ref "C244") (pin "1") (pinfunction "1_1") (pintype "passive"))
      (node (ref "C269") (pin "1") (pinfunction "1_1") (pintype "passive"))
      (node (ref "IC11") (pin "J2") (pinfunction "VREF_J2") (pintype "passive"))
      (node (ref "IC12") (pin "J2") (pinfunction "VREF_J2") (pintype "passive"))
    )
    (net (code "104") (name "GND") (class "Default")
      (node (ref "C221") (pin "2") (pinfunction "2_2") (pintype "passive"))
      (node (ref "C222") (pin "2") (pinfunction "2_2") (pintype "passive"))
      (node (ref "C223") (pin "2") (pinfunction "2_2") (pintype "passive"))
      (node (ref "C224") (pin "2") (pinfunction "2_2") (pintype "passive"))
      (node (ref "C225") (pin "5") (pinfunction "5_5") (pintype "passive"))
      (node (ref "C225") (pin "6") (pinfunction "6_6") (pintype "passive"))
      (node (ref "C225") (pin "7") (pinfunction "7_7") (pintype "passive"))
      (node (ref "C225") (pin "8") (pinfunction "8_8") (pintype "passive"))
      (node (ref "C226") (pin "2") (pinfunction "2_2") (pintype "passive"))
      (node (ref "C227") (pin "2") (pinfunction "2_2") (pintype "passive"))
      (node (ref "C228") (pin "2") (pinfunction "2_2") (pintype "passive"))
      (node (ref "C229") (pin "2") (pinfunction "2_2") (pintype "passive"))
      (node (ref "C230") (pin "5") (pinfunction "5_5") (pintype "passive"))
      (node (ref "C230") (pin "6") (pinfunction "6_6") (pintype "passive"))
      (node (ref "C230") (pin "7") (pinfunction "7_7") (pintype "passive"))
      (node (ref "C230") (pin "8") (pinfunction "8_8") (pintype "passive"))
      (node (ref "C231") (pin "5") (pinfunction "5_5") (pintype "passive"))
      (node (ref "C231") (pin "6") (pinfunction "6_6") (pintype "passive"))
      (node (ref "C231") (pin "7") (pinfunction "7_7") (pintype "passive"))
      (node (ref "C231") (pin "8") (pinfunction "8_8") (pintype "passive"))
      (node (ref "C232") (pin "2") (pinfunction "2_2") (pintype "passive"))
      (node (ref "C233") (pin "2") (pinfunction "2_2") (pintype "passive"))
      (node (ref "C234") (pin "2") (pinfunction "2_2") (pintype "passive"))
      (node (ref "C235") (pin "2") (pinfunction "2_2") (pintype "passive"))
      (node (ref "C236") (pin "2") (pinfunction "2_2") (pintype "passive"))
      (node (ref "C237") (pin "2") (pinfunction "2_2") (pintype "passive"))
      (node (ref "C238") (pin "2") (pinfunction "2_2") (pintype "passive"))
      (node (ref "C239") (pin "2") (pinfunction "2_2") (pintype "passive"))
      (node (ref "C240") (pin "1") (pinfunction "1_1") (pintype "passive"))
      (node (ref "C241") (pin "1") (pinfunction "1_1") (pintype "passive"))
      (node (ref "C242") (pin "1") (pinfunction "1_1") (pintype "passive"))
      (node (ref "C243") (pin "2") (pinfunction "2_2") (pintype "passive"))
      (node (ref "C244") (pin "2") (pinfunction "2_2") (pintype "passive"))
      (node (ref "C245") (pin "1") (pinfunction "1_1") (pintype "passive"))
      (node (ref "C246") (pin "2") (pinfunction "2_2") (pintype "passive"))
      (node (ref "C247") (pin "2") (pinfunction "2_2") (pintype "passive"))
      (node (ref "C248") (pin "2") (pinfunction "2_2") (pintype "passive"))
      (node (ref "C249") (pin "2") (pinfunction "2_2") (pintype "passive"))
      (node (ref "C250") (pin "5") (pinfunction "5_5") (pintype "passive"))
      (node (ref "C250") (pin "6") (pinfunction "6_6") (pintype "passive"))
      (node (ref "C250") (pin "7") (pinfunction "7_7") (pintype "passive"))
      (node (ref "C250") (pin "8") (pinfunction "8_8") (pintype "passive"))
      (node (ref "C251") (pin "2") (pinfunction "2_2") (pintype "passive"))
      (node (ref "C252") (pin "2") (pinfunction "2_2") (pintype "passive"))
      (node (ref "C253") (pin "2") (pinfunction "2_2") (pintype "passive"))
      (node (ref "C254") (pin "2") (pinfunction "2_2") (pintype "passive"))
      (node (ref "C255") (pin "5") (pinfunction "5_5") (pintype "passive"))
      (node (ref "C255") (pin "6") (pinfunction "6_6") (pintype "passive"))
      (node (ref "C255") (pin "7") (pinfunction "7_7") (pintype "passive"))
      (node (ref "C255") (pin "8") (pinfunction "8_8") (pintype "passive"))
      (node (ref "C256") (pin "5") (pinfunction "5_5") (pintype "passive"))
      (node (ref "C256") (pin "6") (pinfunction "6_6") (pintype "passive"))
      (node (ref "C256") (pin "7") (pinfunction "7_7") (pintype "passive"))
      (node (ref "C256") (pin "8") (pinfunction "8_8") (pintype "passive"))
      (node (ref "C257") (pin "2") (pinfunction "2_2") (pintype "passive"))
      (node (ref "C258") (pin "2") (pinfunction "2_2") (pintype "passive"))
      (node (ref "C259") (pin "2") (pinfunction "2_2") (pintype "passive"))
      (node (ref "C260") (pin "2") (pinfunction "2_2") (pintype "passive"))
      (node (ref "C261") (pin "2") (pinfunction "2_2") (pintype "passive"))
      (node (ref "C262") (pin "2") (pinfunction "2_2") (pintype "passive"))
      (node (ref "C263") (pin "2") (pinfunction "2_2") (pintype "passive"))
      (node (ref "C264") (pin "2") (pinfunction "2_2") (pintype "passive"))
      (node (ref "C265") (pin "1") (pinfunction "1_1") (pintype "passive"))
      (node (ref "C266") (pin "1") (pinfunction "1_1") (pintype "passive"))
      (node (ref "C267") (pin "1") (pinfunction "1_1") (pintype "passive"))
      (node (ref "C268") (pin "2") (pinfunction "2_2") (pintype "passive"))
      (node (ref "C269") (pin "2") (pinfunction "2_2") (pintype "passive"))
      (node (ref "IC11") (pin "A3") (pinfunction "VSS_A3") (pintype "power_in"))
      (node (ref "IC11") (pin "A7") (pinfunction "VSSQ_A7") (pintype "power_in"))
      (node (ref "IC11") (pin "B2") (pinfunction "VSSQ_B2") (pintype "power_in"))
      (node (ref "IC11") (pin "B8") (pinfunction "VSSQ_B8") (pintype "power_in"))
      (node (ref "IC11") (pin "D2") (pinfunction "VSSQ_D2") (pintype "power_in"))
      (node (ref "IC11") (pin "D8") (pinfunction "VSSQ_D8") (pintype "power_in"))
      (node (ref "IC11") (pin "E3") (pinfunction "VSS_E3") (pintype "power_in"))
      (node (ref "IC11") (pin "E7") (pinfunction "VSSQ_E7") (pintype "power_in"))
      (node (ref "IC11") (pin "F2") (pinfunction "VSSQ_F2") (pintype "power_in"))
      (node (ref "IC11") (pin "F8") (pinfunction "VSSQ_F8") (pintype "power_in"))
      (node (ref "IC11") (pin "H2") (pinfunction "VSSQ_H2") (pintype "power_in"))
      (node (ref "IC11") (pin "H8") (pinfunction "VSSQ_H8") (pintype "power_in"))
      (node (ref "IC11") (pin "J3") (pinfunction "VSS_J3") (pintype "power_in"))
      (node (ref "IC11") (pin "J7") (pinfunction "VSSDL_J7") (pintype "power_in"))
      (node (ref "IC11") (pin "N1") (pinfunction "VSS_N1") (pintype "power_in"))
      (node (ref "IC11") (pin "P9") (pinfunction "VSS_P9") (pintype "power_in"))
      (node (ref "IC12") (pin "A3") (pinfunction "VSS_A3") (pintype "power_in"))
      (node (ref "IC12") (pin "A7") (pinfunction "VSSQ_A7") (pintype "power_in"))
      (node (ref "IC12") (pin "B2") (pinfunction "VSSQ_B2") (pintype "power_in"))
      (node (ref "IC12") (pin "B8") (pinfunction "VSSQ_B8") (pintype "power_in"))
      (node (ref "IC12") (pin "D2") (pinfunction "VSSQ_D2") (pintype "power_in"))
      (node (ref "IC12") (pin "D8") (pinfunction "VSSQ_D8") (pintype "power_in"))
      (node (ref "IC12") (pin "E3") (pinfunction "VSS_E3") (pintype "power_in"))
      (node (ref "IC12") (pin "E7") (pinfunction "VSSQ_E7") (pintype "power_in"))
      (node (ref "IC12") (pin "F2") (pinfunction "VSSQ_F2") (pintype "power_in"))
      (node (ref "IC12") (pin "F8") (pinfunction "VSSQ_F8") (pintype "power_in"))
      (node (ref "IC12") (pin "H2") (pinfunction "VSSQ_H2") (pintype "power_in"))
      (node (ref "IC12") (pin "H8") (pinfunction "VSSQ_H8") (pintype "power_in"))
      (node (ref "IC12") (pin "J3") (pinfunction "VSS_J3") (pintype "power_in"))
      (node (ref "IC12") (pin "J7") (pinfunction "VSSDL_J7") (pintype "power_in"))
      (node (ref "IC12") (pin "N1") (pinfunction "VSS_N1") (pintype "power_in"))
      (node (ref "IC12") (pin "P9") (pinfunction "VSS_P9") (pintype "power_in"))
      (node (ref "R79") (pin "1") (pinfunction "1_1") (pintype "passive"))
      (node (ref "R80") (pin "1") (pinfunction "1_1") (pintype "passive"))
      (node (ref "R85") (pin "1") (pinfunction "1_1") (pintype "passive"))
      (node (ref "R86") (pin "1") (pinfunction "1_1") (pintype "passive"))
    )
    (net (code "105") (name "VCC1P8_DDR2") (class "Default")
      (node (ref "C221") (pin "1") (pinfunction "1_1") (pintype "passive"))
      (node (ref "C222") (pin "1") (pinfunction "1_1") (pintype "passive"))
      (node (ref "C223") (pin "1") (pinfunction "1_1") (pintype "passive"))
      (node (ref "C224") (pin "1") (pinfunction "1_1") (pintype "passive"))
      (node (ref "C226") (pin "1") (pinfunction "1_1") (pintype "passive"))
      (node (ref "C227") (pin "1") (pinfunction "1_1") (pintype "passive"))
      (node (ref "C228") (pin "1") (pinfunction "1_1") (pintype "passive"))
      (node (ref "C229") (pin "1") (pinfunction "1_1") (pintype "passive"))
      (node (ref "C232") (pin "1") (pinfunction "1_1") (pintype "passive"))
      (node (ref "C233") (pin "1") (pinfunction "1_1") (pintype "passive"))
      (node (ref "C234") (pin "1") (pinfunction "1_1") (pintype "passive"))
      (node (ref "C235") (pin "1") (pinfunction "1_1") (pintype "passive"))
      (node (ref "C236") (pin "1") (pinfunction "1_1") (pintype "passive"))
      (node (ref "C237") (pin "1") (pinfunction "1_1") (pintype "passive"))
      (node (ref "C238") (pin "1") (pinfunction "1_1") (pintype "passive"))
      (node (ref "C239") (pin "1") (pinfunction "1_1") (pintype "passive"))
      (node (ref "C240") (pin "2") (pinfunction "2_2") (pintype "passive"))
      (node (ref "C241") (pin "2") (pinfunction "2_2") (pintype "passive"))
      (node (ref "C242") (pin "2") (pinfunction "2_2") (pintype "passive"))
      (node (ref "C243") (pin "1") (pinfunction "1_1") (pintype "passive"))
      (node (ref "C245") (pin "2") (pinfunction "2_2") (pintype "passive"))
      (node (ref "C246") (pin "1") (pinfunction "1_1") (pintype "passive"))
      (node (ref "C247") (pin "1") (pinfunction "1_1") (pintype "passive"))
      (node (ref "C248") (pin "1") (pinfunction "1_1") (pintype "passive"))
      (node (ref "C249") (pin "1") (pinfunction "1_1") (pintype "passive"))
      (node (ref "C251") (pin "1") (pinfunction "1_1") (pintype "passive"))
      (node (ref "C252") (pin "1") (pinfunction "1_1") (pintype "passive"))
      (node (ref "C253") (pin "1") (pinfunction "1_1") (pintype "passive"))
      (node (ref "C254") (pin "1") (pinfunction "1_1") (pintype "passive"))
      (node (ref "C257") (pin "1") (pinfunction "1_1") (pintype "passive"))
      (node (ref "C258") (pin "1") (pinfunction "1_1") (pintype "passive"))
      (node (ref "C259") (pin "1") (pinfunction "1_1") (pintype "passive"))
      (node (ref "C260") (pin "1") (pinfunction "1_1") (pintype "passive"))
      (node (ref "C261") (pin "1") (pinfunction "1_1") (pintype "passive"))
      (node (ref "C262") (pin "1") (pinfunction "1_1") (pintype "passive"))
      (node (ref "C263") (pin "1") (pinfunction "1_1") (pintype "passive"))
      (node (ref "C264") (pin "1") (pinfunction "1_1") (pintype "passive"))
      (node (ref "C265") (pin "2") (pinfunction "2_2") (pintype "passive"))
      (node (ref "C266") (pin "2") (pinfunction "2_2") (pintype "passive"))
      (node (ref "C267") (pin "2") (pinfunction "2_2") (pintype "passive"))
      (node (ref "C268") (pin "1") (pinfunction "1_1") (pintype "passive"))
      (node (ref "IC11") (pin "A1") (pinfunction "VDD_A1") (pintype "power_in"))
      (node (ref "IC11") (pin "A9") (pinfunction "VDDQ_A9") (pintype "power_in"))
      (node (ref "IC11") (pin "C1") (pinfunction "VDDQ_C1") (pintype "power_in"))
      (node (ref "IC11") (pin "C3") (pinfunction "VDDQ_C3") (pintype "power_in"))
      (node (ref "IC11") (pin "C7") (pinfunction "VDDQ_C7") (pintype "power_in"))
      (node (ref "IC11") (pin "C9") (pinfunction "VDDQ_C9") (pintype "power_in"))
      (node (ref "IC11") (pin "E1") (pinfunction "VDD_E1") (pintype "power_in"))
      (node (ref "IC11") (pin "E9") (pinfunction "VDDQ_E9") (pintype "power_in"))
      (node (ref "IC11") (pin "G1") (pinfunction "VDDQ_G1") (pintype "power_in"))
      (node (ref "IC11") (pin "G3") (pinfunction "VDDQ_G3") (pintype "power_in"))
      (node (ref "IC11") (pin "G7") (pinfunction "VDDQ_G7") (pintype "power_in"))
      (node (ref "IC11") (pin "G9") (pinfunction "VDDQ_G9") (pintype "power_in"))
      (node (ref "IC11") (pin "J1") (pinfunction "VDDL_J1") (pintype "power_in"))
      (node (ref "IC11") (pin "J9") (pinfunction "VDD_J9") (pintype "power_in"))
      (node (ref "IC11") (pin "M9") (pinfunction "VDD_M9") (pintype "power_in"))
      (node (ref "IC11") (pin "R1") (pinfunction "VDD_R1") (pintype "power_in"))
      (node (ref "IC12") (pin "A1") (pinfunction "VDD_A1") (pintype "power_in"))
      (node (ref "IC12") (pin "A9") (pinfunction "VDDQ_A9") (pintype "power_in"))
      (node (ref "IC12") (pin "C1") (pinfunction "VDDQ_C1") (pintype "power_in"))
      (node (ref "IC12") (pin "C3") (pinfunction "VDDQ_C3") (pintype "power_in"))
      (node (ref "IC12") (pin "C7") (pinfunction "VDDQ_C7") (pintype "power_in"))
      (node (ref "IC12") (pin "C9") (pinfunction "VDDQ_C9") (pintype "power_in"))
      (node (ref "IC12") (pin "E1") (pinfunction "VDD_E1") (pintype "power_in"))
      (node (ref "IC12") (pin "E9") (pinfunction "VDDQ_E9") (pintype "power_in"))
      (node (ref "IC12") (pin "G1") (pinfunction "VDDQ_G1") (pintype "power_in"))
      (node (ref "IC12") (pin "G3") (pinfunction "VDDQ_G3") (pintype "power_in"))
      (node (ref "IC12") (pin "G7") (pinfunction "VDDQ_G7") (pintype "power_in"))
      (node (ref "IC12") (pin "G9") (pinfunction "VDDQ_G9") (pintype "power_in"))
      (node (ref "IC12") (pin "J1") (pinfunction "VDDL_J1") (pintype "power_in"))
      (node (ref "IC12") (pin "J9") (pinfunction "VDD_J9") (pintype "power_in"))
      (node (ref "IC12") (pin "M9") (pinfunction "VDD_M9") (pintype "power_in"))
      (node (ref "IC12") (pin "R1") (pinfunction "VDD_R1") (pintype "power_in"))
    )
    (net (code "106") (name "VTT_DDR2") (class "Default")
      (node (ref "C225") (pin "1") (pinfunction "1_1") (pintype "passive"))
      (node (ref "C225") (pin "2") (pinfunction "2_2") (pintype "passive"))
      (node (ref "C225") (pin "3") (pinfunction "3_3") (pintype "passive"))
      (node (ref "C225") (pin "4") (pinfunction "4_4") (pintype "passive"))
      (node (ref "C230") (pin "1") (pinfunction "1_1") (pintype "passive"))
      (node (ref "C230") (pin "2") (pinfunction "2_2") (pintype "passive"))
      (node (ref "C230") (pin "3") (pinfunction "3_3") (pintype "passive"))
      (node (ref "C230") (pin "4") (pinfunction "4_4") (pintype "passive"))
      (node (ref "C231") (pin "1") (pinfunction "1_1") (pintype "passive"))
      (node (ref "C231") (pin "2") (pinfunction "2_2") (pintype "passive"))
      (node (ref "C231") (pin "3") (pinfunction "3_3") (pintype "passive"))
      (node (ref "C231") (pin "4") (pinfunction "4_4") (pintype "passive"))
      (node (ref "C250") (pin "1") (pinfunction "1_1") (pintype "passive"))
      (node (ref "C250") (pin "2") (pinfunction "2_2") (pintype "passive"))
      (node (ref "C250") (pin "3") (pinfunction "3_3") (pintype "passive"))
      (node (ref "C250") (pin "4") (pinfunction "4_4") (pintype "passive"))
      (node (ref "C255") (pin "1") (pinfunction "1_1") (pintype "passive"))
      (node (ref "C255") (pin "2") (pinfunction "2_2") (pintype "passive"))
      (node (ref "C255") (pin "3") (pinfunction "3_3") (pintype "passive"))
      (node (ref "C255") (pin "4") (pinfunction "4_4") (pintype "passive"))
      (node (ref "C256") (pin "1") (pinfunction "1_1") (pintype "passive"))
      (node (ref "C256") (pin "2") (pinfunction "2_2") (pintype "passive"))
      (node (ref "C256") (pin "3") (pinfunction "3_3") (pintype "passive"))
      (node (ref "C256") (pin "4") (pinfunction "4_4") (pintype "passive"))
      (node (ref "R75") (pin "10") (pinfunction "10_10") (pintype "passive"))
      (node (ref "R75") (pin "11") (pinfunction "11_11") (pintype "passive"))
      (node (ref "R75") (pin "12") (pinfunction "12_12") (pintype "passive"))
      (node (ref "R75") (pin "13") (pinfunction "13_13") (pintype "passive"))
      (node (ref "R75") (pin "14") (pinfunction "14_14") (pintype "passive"))
      (node (ref "R75") (pin "15") (pinfunction "15_15") (pintype "passive"))
      (node (ref "R75") (pin "16") (pinfunction "16_16") (pintype "passive"))
      (node (ref "R75") (pin "9") (pinfunction "9_9") (pintype "passive"))
      (node (ref "R77") (pin "10") (pinfunction "10_10") (pintype "passive"))
      (node (ref "R77") (pin "11") (pinfunction "11_11") (pintype "passive"))
      (node (ref "R77") (pin "12") (pinfunction "12_12") (pintype "passive"))
      (node (ref "R77") (pin "13") (pinfunction "13_13") (pintype "passive"))
      (node (ref "R77") (pin "14") (pinfunction "14_14") (pintype "passive"))
      (node (ref "R77") (pin "15") (pinfunction "15_15") (pintype "passive"))
      (node (ref "R77") (pin "16") (pinfunction "16_16") (pintype "passive"))
      (node (ref "R77") (pin "9") (pinfunction "9_9") (pintype "passive"))
      (node (ref "R78") (pin "10") (pinfunction "10_10") (pintype "passive"))
      (node (ref "R78") (pin "11") (pinfunction "11_11") (pintype "passive"))
      (node (ref "R78") (pin "12") (pinfunction "12_12") (pintype "passive"))
      (node (ref "R78") (pin "13") (pinfunction "13_13") (pintype "passive"))
      (node (ref "R78") (pin "14") (pinfunction "14_14") (pintype "passive"))
      (node (ref "R78") (pin "15") (pinfunction "15_15") (pintype "passive"))
      (node (ref "R78") (pin "16") (pinfunction "16_16") (pintype "passive"))
      (node (ref "R78") (pin "9") (pinfunction "9_9") (pintype "passive"))
      (node (ref "R81") (pin "10") (pinfunction "10_10") (pintype "passive"))
      (node (ref "R81") (pin "11") (pinfunction "11_11") (pintype "passive"))
      (node (ref "R81") (pin "12") (pinfunction "12_12") (pintype "passive"))
      (node (ref "R81") (pin "13") (pinfunction "13_13") (pintype "passive"))
      (node (ref "R81") (pin "14") (pinfunction "14_14") (pintype "passive"))
      (node (ref "R81") (pin "15") (pinfunction "15_15") (pintype "passive"))
      (node (ref "R81") (pin "16") (pinfunction "16_16") (pintype "passive"))
      (node (ref "R81") (pin "9") (pinfunction "9_9") (pintype "passive"))
      (node (ref "R83") (pin "10") (pinfunction "10_10") (pintype "passive"))
      (node (ref "R83") (pin "11") (pinfunction "11_11") (pintype "passive"))
      (node (ref "R83") (pin "12") (pinfunction "12_12") (pintype "passive"))
      (node (ref "R83") (pin "13") (pinfunction "13_13") (pintype "passive"))
      (node (ref "R83") (pin "14") (pinfunction "14_14") (pintype "passive"))
      (node (ref "R83") (pin "15") (pinfunction "15_15") (pintype "passive"))
      (node (ref "R83") (pin "16") (pinfunction "16_16") (pintype "passive"))
      (node (ref "R83") (pin "9") (pinfunction "9_9") (pintype "passive"))
      (node (ref "R84") (pin "10") (pinfunction "10_10") (pintype "passive"))
      (node (ref "R84") (pin "11") (pinfunction "11_11") (pintype "passive"))
      (node (ref "R84") (pin "12") (pinfunction "12_12") (pintype "passive"))
      (node (ref "R84") (pin "13") (pinfunction "13_13") (pintype "passive"))
      (node (ref "R84") (pin "14") (pinfunction "14_14") (pintype "passive"))
      (node (ref "R84") (pin "15") (pinfunction "15_15") (pintype "passive"))
      (node (ref "R84") (pin "16") (pinfunction "16_16") (pintype "passive"))
      (node (ref "R84") (pin "9") (pinfunction "9_9") (pintype "passive"))
    )
    (net (code "107") (name "unconnected-(IC11B-NC-PadA2)") (class "Default")
      (node (ref "IC11") (pin "A2") (pinfunction "NC_A2") (pintype "passive+no_connect"))
    )
    (net (code "108") (name "unconnected-(IC11B-NC-PadE2)") (class "Default")
      (node (ref "IC11") (pin "E2") (pinfunction "NC_E2") (pintype "passive+no_connect"))
    )
    (net (code "109") (name "unconnected-(IC11B-NC-PadR3)") (class "Default")
      (node (ref "IC11") (pin "R3") (pinfunction "NC_R3") (pintype "passive+no_connect"))
    )
    (net (code "110") (name "unconnected-(IC11B-NC-PadR7)") (class "Default")
      (node (ref "IC11") (pin "R7") (pinfunction "NC_R7") (pintype "passive+no_connect"))
    )
    (net (code "111") (name "unconnected-(IC11B-NC-PadR8)") (class "Default")
      (node (ref "IC11") (pin "R8") (pinfunction "NC_R8") (pintype "passive+no_connect"))
    )
    (net (code "112") (name "unconnected-(IC12B-NC-PadA2)") (class "Default")
      (node (ref "IC12") (pin "A2") (pinfunction "NC_A2") (pintype "passive+no_connect"))
    )
    (net (code "113") (name "unconnected-(IC12B-NC-PadE2)") (class "Default")
      (node (ref "IC12") (pin "E2") (pinfunction "NC_E2") (pintype "passive+no_connect"))
    )
    (net (code "114") (name "unconnected-(IC12B-NC-PadR3)") (class "Default")
      (node (ref "IC12") (pin "R3") (pinfunction "NC_R3") (pintype "passive+no_connect"))
    )
    (net (code "115") (name "unconnected-(IC12B-NC-PadR7)") (class "Default")
      (node (ref "IC12") (pin "R7") (pinfunction "NC_R7") (pintype "passive+no_connect"))
    )
    (net (code "116") (name "unconnected-(IC12B-NC-PadR8)") (class "Default")
      (node (ref "IC12") (pin "R8") (pinfunction "NC_R8") (pintype "passive+no_connect"))
    )
    (net (code "117") (name "unconnected-(R78-Pad7)") (class "Default")
      (node (ref "R78") (pin "7") (pinfunction "7_7") (pintype "passive+no_connect"))
    )
    (net (code "118") (name "unconnected-(R78-Pad8)") (class "Default")
      (node (ref "R78") (pin "8") (pinfunction "8_8") (pintype "passive+no_connect"))
    )
    (net (code "119") (name "unconnected-(R84-Pad1)") (class "Default")
      (node (ref "R84") (pin "1") (pinfunction "1_1") (pintype "passive+no_connect"))
    )
    (net (code "120") (name "unconnected-(R84-Pad7)") (class "Default")
      (node (ref "R84") (pin "7") (pinfunction "7_7") (pintype "passive+no_connect"))
    )
  )
)
